# MainBoard_v2_0_RevB.net
KiCad netlist of a schematic drawn in EAGLE
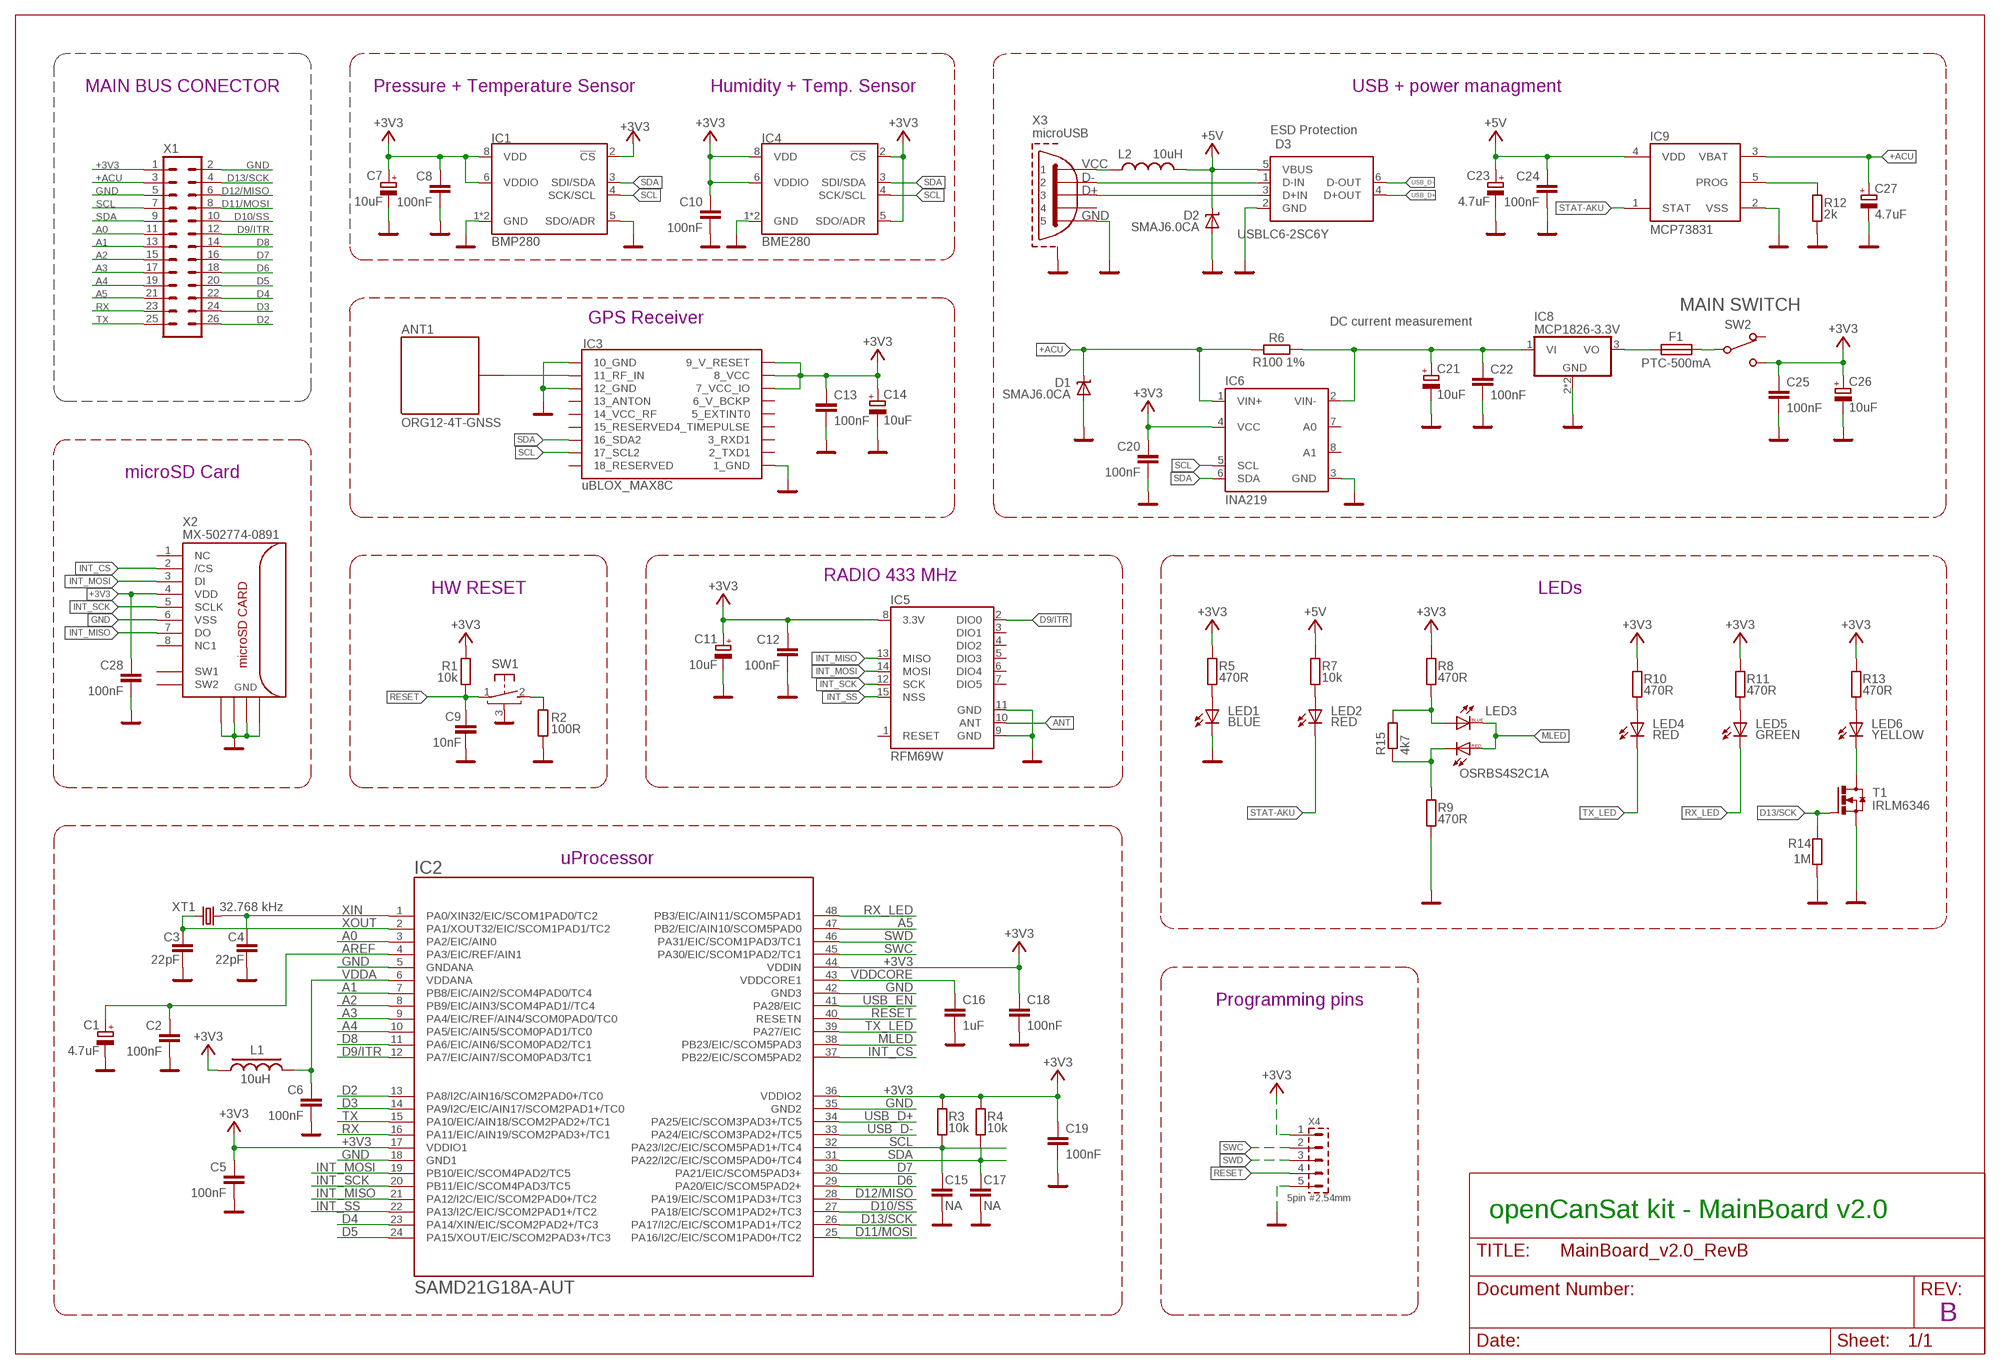
[diagram p0: schematic, sheet 1]

(export (version "E")
  (design (tool "Eeschema 10.0.6"))
  (components
    (comp (ref "ANT1")
      (value "ORG12-4T-GNSS")
      (footprint "eagle-import:ANT_GPS_12X12")
      (libsource (lib "eagle-import") (part "GPS_ANT"))
    )
    (comp (ref "C1")
      (value "4.7uF")
      (footprint "eagle-import:SMC_A")
      (libsource (lib "eagle-import") (part "CPOL-EUSMCA"))
    )
    (comp (ref "C2")
      (value "100nF")
      (footprint "eagle-import:C0603")
      (libsource (lib "eagle-import") (part "C-EUC0603"))
    )
    (comp (ref "C3")
      (value "22pF")
      (footprint "eagle-import:C0603")
      (libsource (lib "eagle-import") (part "C-EUC0603"))
    )
    (comp (ref "C4")
      (value "22pF")
      (footprint "eagle-import:C0603")
      (libsource (lib "eagle-import") (part "C-EUC0603"))
    )
    (comp (ref "C5")
      (value "100nF")
      (footprint "eagle-import:C0603")
      (libsource (lib "eagle-import") (part "C-EUC0603"))
    )
    (comp (ref "C6")
      (value "100nF")
      (footprint "eagle-import:C0603")
      (libsource (lib "eagle-import") (part "C-EUC0603"))
    )
    (comp (ref "C7")
      (value "10uF")
      (footprint "eagle-import:SMC_A")
      (libsource (lib "eagle-import") (part "CPOL-EUSMCA"))
    )
    (comp (ref "C8")
      (value "100nF")
      (footprint "eagle-import:C0603")
      (libsource (lib "eagle-import") (part "C-EUC0603"))
    )
    (comp (ref "C9")
      (value "10nF")
      (footprint "eagle-import:C0603")
      (libsource (lib "eagle-import") (part "C-EUC0603"))
    )
    (comp (ref "C10")
      (value "100nF")
      (footprint "eagle-import:C0603")
      (libsource (lib "eagle-import") (part "C-EUC0603"))
    )
    (comp (ref "C11")
      (value "10uF")
      (footprint "eagle-import:SMC_A")
      (libsource (lib "eagle-import") (part "CPOL-EUSMCA"))
    )
    (comp (ref "C12")
      (value "100nF")
      (footprint "eagle-import:C0603")
      (libsource (lib "eagle-import") (part "C-EUC0603"))
    )
    (comp (ref "C13")
      (value "100nF")
      (footprint "eagle-import:C0603")
      (libsource (lib "eagle-import") (part "C-EUC0603"))
    )
    (comp (ref "C14")
      (value "10uF")
      (footprint "eagle-import:SMC_A")
      (libsource (lib "eagle-import") (part "CPOL-EUSMCA"))
    )
    (comp (ref "C15")
      (value "NA")
      (footprint "eagle-import:C0603")
      (libsource (lib "eagle-import") (part "C-EUC0603"))
    )
    (comp (ref "C16")
      (value "1uF")
      (footprint "eagle-import:C0805")
      (libsource (lib "eagle-import") (part "C-EUC0805"))
    )
    (comp (ref "C17")
      (value "NA")
      (footprint "eagle-import:C0603")
      (libsource (lib "eagle-import") (part "C-EUC0603"))
    )
    (comp (ref "C18")
      (value "100nF")
      (footprint "eagle-import:C0603")
      (libsource (lib "eagle-import") (part "C-EUC0603"))
    )
    (comp (ref "C19")
      (value "100nF")
      (footprint "eagle-import:C0603")
      (libsource (lib "eagle-import") (part "C-EUC0603"))
    )
    (comp (ref "C20")
      (value "100nF")
      (footprint "eagle-import:C0603")
      (libsource (lib "eagle-import") (part "C-EUC0603"))
    )
    (comp (ref "C21")
      (value "10uF")
      (footprint "eagle-import:SMC_B")
      (libsource (lib "eagle-import") (part "CPOL-EUSMCB"))
    )
    (comp (ref "C22")
      (value "100nF")
      (footprint "eagle-import:C0603")
      (libsource (lib "eagle-import") (part "C-EUC0603"))
    )
    (comp (ref "C23")
      (value "4.7uF")
      (footprint "eagle-import:SMC_A")
      (libsource (lib "eagle-import") (part "CPOL-EUSMCA"))
    )
    (comp (ref "C24")
      (value "100nF")
      (footprint "eagle-import:C0603")
      (libsource (lib "eagle-import") (part "C-EUC0603"))
    )
    (comp (ref "C25")
      (value "100nF")
      (footprint "eagle-import:C0603")
      (libsource (lib "eagle-import") (part "C-EUC0603"))
    )
    (comp (ref "C26")
      (value "10uF")
      (footprint "eagle-import:SMC_B")
      (libsource (lib "eagle-import") (part "CPOL-EUSMCB"))
    )
    (comp (ref "C27")
      (value "4.7uF")
      (footprint "eagle-import:SMC_A")
      (libsource (lib "eagle-import") (part "CPOL-EUSMCA"))
    )
    (comp (ref "C28")
      (value "100nF")
      (footprint "eagle-import:C0603")
      (libsource (lib "eagle-import") (part "C-EUC0603"))
    )
    (comp (ref "D1")
      (value "SMAJ6.0CA")
      (footprint "eagle-import:DO214AC")
      (libsource (lib "eagle-import") (part "TRANSILDO214AC"))
    )
    (comp (ref "D2")
      (value "SMAJ6.0CA")
      (footprint "eagle-import:DO214AC")
      (libsource (lib "eagle-import") (part "TRANSILDO214AC"))
    )
    (comp (ref "D3")
      (value "USBLC6-2SC6Y")
      (footprint "eagle-import:SOT95P280X145-6N")
      (fields (field (name "RS_PART_NUMBER") "8805525"))
      (libsource (lib "eagle-import") (part "USBLC6-2SC6Y"))
    )
    (comp (ref "F1")
      (value "PTC-500mA")
      (footprint "eagle-import:1210")
      (libsource (lib "eagle-import") (part "FUZE1210"))
    )
    (comp (ref "IC1")
      (value "BMP280")
      (footprint "eagle-import:LGA-8-2.5X2.5")
      (libsource (lib "eagle-import") (part "BME280"))
    )
    (comp (ref "IC2")
      (value "SAMD21G18A-AUT")
      (footprint "eagle-import:TQFP48-7X7")
      (libsource (lib "eagle-import") (part "1792_SAMD21G18A-AUT"))
    )
    (comp (ref "IC3")
      (value "uBLOX_MAX8C")
      (footprint "eagle-import:UBLOX_MAX-6")
      (libsource (lib "eagle-import") (part "UBLOX_MAX-6"))
    )
    (comp (ref "IC4")
      (value "BME280")
      (footprint "eagle-import:LGA-8-2.5X2.5")
      (libsource (lib "eagle-import") (part "BME280"))
    )
    (comp (ref "IC5")
      (value "RFM69W")
      (footprint "eagle-import:RFM69W-XXXS2")
      (libsource (lib "eagle-import") (part "RFM69HW"))
    )
    (comp (ref "IC6")
      (value "INA219")
      (footprint "eagle-import:SOT23-8")
      (libsource (lib "eagle-import") (part "INA219"))
    )
    (comp (ref "IC8")
      (value "MCP1826-3.3V")
      (footprint "eagle-import:SOT223-3")
      (libsource (lib "eagle-import") (part "MCP1826SOT223-3"))
    )
    (comp (ref "IC9")
      (value "MCP73831")
      (footprint "eagle-import:SOT23-5L")
      (libsource (lib "eagle-import") (part "MCP73831/OT"))
    )
    (comp (ref "L1")
      (value "10uH")
      (footprint "eagle-import:R0805")
      (libsource (lib "eagle-import") (part "L-USL0805"))
    )
    (comp (ref "L2")
      (value "10uH")
      (footprint "eagle-import:R0805")
      (libsource (lib "eagle-import") (part "L-USL0805"))
    )
    (comp (ref "LED1")
      (value "BLUE")
      (footprint "eagle-import:CHIPLED_0603")
      (libsource (lib "eagle-import") (part "LEDCHIPLED_0603"))
    )
    (comp (ref "LED2")
      (value "RED")
      (footprint "eagle-import:CHIPLED_0603")
      (libsource (lib "eagle-import") (part "LEDCHIPLED_0603"))
    )
    (comp (ref "LED3")
      (value "OSRBS4S2C1A")
      (footprint "eagle-import:PLCC4")
      (libsource (lib "eagle-import") (part "OSRBS4S2C1A"))
    )
    (comp (ref "LED4")
      (value "RED")
      (footprint "eagle-import:CHIPLED_0603")
      (libsource (lib "eagle-import") (part "LEDCHIPLED_0603"))
    )
    (comp (ref "LED5")
      (value "GREEN")
      (footprint "eagle-import:CHIPLED_0603")
      (libsource (lib "eagle-import") (part "LEDCHIPLED_0603"))
    )
    (comp (ref "LED6")
      (value "YELLOW")
      (footprint "eagle-import:CHIPLED_0603")
      (libsource (lib "eagle-import") (part "LEDCHIPLED_0603"))
    )
    (comp (ref "R1")
      (value "10k")
      (footprint "eagle-import:R0603")
      (libsource (lib "eagle-import") (part "R-EU_R0603"))
    )
    (comp (ref "R2")
      (value "100R")
      (footprint "eagle-import:R0603")
      (libsource (lib "eagle-import") (part "R-EU_R0603"))
    )
    (comp (ref "R3")
      (value "10k")
      (footprint "eagle-import:R0603")
      (libsource (lib "eagle-import") (part "R-EU_R0603"))
    )
    (comp (ref "R4")
      (value "10k")
      (footprint "eagle-import:R0603")
      (libsource (lib "eagle-import") (part "R-EU_R0603"))
    )
    (comp (ref "R5")
      (value "470R")
      (footprint "eagle-import:R0603")
      (libsource (lib "eagle-import") (part "R-EU_R0603"))
    )
    (comp (ref "R6")
      (value "R100 1%")
      (footprint "eagle-import:R2010")
      (libsource (lib "eagle-import") (part "R-EU_R2010"))
    )
    (comp (ref "R7")
      (value "10k")
      (footprint "eagle-import:R0603")
      (libsource (lib "eagle-import") (part "R-EU_R0603"))
    )
    (comp (ref "R8")
      (value "470R")
      (footprint "eagle-import:R0603")
      (libsource (lib "eagle-import") (part "R-EU_R0603"))
    )
    (comp (ref "R9")
      (value "470R")
      (footprint "eagle-import:R0603")
      (libsource (lib "eagle-import") (part "R-EU_R0603"))
    )
    (comp (ref "R10")
      (value "470R")
      (footprint "eagle-import:R0603")
      (libsource (lib "eagle-import") (part "R-EU_R0603"))
    )
    (comp (ref "R11")
      (value "470R")
      (footprint "eagle-import:R0603")
      (libsource (lib "eagle-import") (part "R-EU_R0603"))
    )
    (comp (ref "R12")
      (value "2k")
      (footprint "eagle-import:R0603")
      (libsource (lib "eagle-import") (part "R-EU_R0603"))
    )
    (comp (ref "R13")
      (value "470R")
      (footprint "eagle-import:R0603")
      (libsource (lib "eagle-import") (part "R-EU_R0603"))
    )
    (comp (ref "R14")
      (value "1M")
      (footprint "eagle-import:R0603")
      (libsource (lib "eagle-import") (part "R-EU_R0603"))
    )
    (comp (ref "R15")
      (value "4k7")
      (footprint "eagle-import:R0603")
      (libsource (lib "eagle-import") (part "R-EU_R0603"))
    )
    (comp (ref "SW1")
      (value "B3U-3100P")
      (footprint "eagle-import:B3U-3100PM")
      (libsource (lib "eagle-import") (part "B3U-3100P"))
    )
    (comp (ref "SW2")
      (value "MSS-1290")
      (footprint "eagle-import:MSS-1290")
      (libsource (lib "eagle-import") (part "MSS-1290"))
    )
    (comp (ref "T1")
      (value "IRLM6346")
      (footprint "eagle-import:SOT23")
      (libsource (lib "eagle-import") (part "IRLML6346"))
    )
    (comp (ref "X1")
      (value "MA13-2SMD")
      (footprint "eagle-import:MA13-2")
      (libsource (lib "eagle-import") (part "MA13-2SMD"))
    )
    (comp (ref "X2")
      (value "MX-502774-0891")
      (footprint "eagle-import:502774-0891")
      (libsource (lib "eagle-import") (part "MICROSD"))
    )
    (comp (ref "X3")
      (value "microUSB")
      (footprint "eagle-import:1981568-MICROUSB")
      (libsource (lib "eagle-import") (part "MICROUSB1981568"))
    )
    (comp (ref "X4")
      (value "5pin #2.54mm")
      (footprint "eagle-import:PIN5")
      (libsource (lib "eagle-import") (part "S1G5_JUMPSMD"))
    )
    (comp (ref "XT1")
      (value "32.768 kHz")
      (footprint "eagle-import:XTAL35X15")
      (libsource (lib "eagle-import") (part "XTAL32KHZ"))
    )
  )
  (nets
    (net (code "1") (name "+3V3") (class "Default")
      (node (ref "C10") (pin "1") (pinfunction "1_1") (pintype "passive"))
      (node (ref "C11") (pin "+") (pinfunction "+_+") (pintype "passive"))
      (node (ref "C12") (pin "1") (pinfunction "1_1") (pintype "passive"))
      (node (ref "C13") (pin "1") (pinfunction "1_1") (pintype "passive"))
      (node (ref "C14") (pin "+") (pinfunction "+_+") (pintype "passive"))
      (node (ref "C18") (pin "1") (pinfunction "1_1") (pintype "passive"))
      (node (ref "C19") (pin "1") (pinfunction "1_1") (pintype "passive"))
      (node (ref "C20") (pin "1") (pinfunction "1_1") (pintype "passive"))
      (node (ref "C25") (pin "1") (pinfunction "1_1") (pintype "passive"))
      (node (ref "C26") (pin "+") (pinfunction "+_+") (pintype "passive"))
      (node (ref "C28") (pin "1") (pinfunction "1_1") (pintype "passive"))
      (node (ref "C5") (pin "1") (pinfunction "1_1") (pintype "passive"))
      (node (ref "C7") (pin "+") (pinfunction "+_+") (pintype "passive"))
      (node (ref "C8") (pin "1") (pinfunction "1_1") (pintype "passive"))
      (node (ref "IC1") (pin "2") (pinfunction "~{CS}_2") (pintype "bidirectional"))
      (node (ref "IC1") (pin "6") (pinfunction "VDDIO_6") (pintype "bidirectional"))
      (node (ref "IC1") (pin "8") (pinfunction "VDD_8") (pintype "bidirectional"))
      (node (ref "IC2") (pin "17") (pinfunction "VDDIO1_17") (pintype "power_in"))
      (node (ref "IC2") (pin "36") (pinfunction "VDDIO2_36") (pintype "power_in"))
      (node (ref "IC2") (pin "44") (pinfunction "VDDIN_44") (pintype "power_in"))
      (node (ref "IC3") (pin "7_VCC_IO") (pinfunction "7_VCC_IO_7_VCC_IO") (pintype "power_in"))
      (node (ref "IC3") (pin "8_VCC") (pinfunction "8_VCC_8_VCC") (pintype "power_in"))
      (node (ref "IC3") (pin "9_V_RESET") (pinfunction "9_V_RESET_9_V_RESET") (pintype "power_in"))
      (node (ref "IC4") (pin "2") (pinfunction "~{CS}_2") (pintype "bidirectional"))
      (node (ref "IC4") (pin "5") (pinfunction "SDO/ADR_5") (pintype "bidirectional"))
      (node (ref "IC4") (pin "6") (pinfunction "VDDIO_6") (pintype "bidirectional"))
      (node (ref "IC4") (pin "8") (pinfunction "VDD_8") (pintype "bidirectional"))
      (node (ref "IC5") (pin "8") (pinfunction "3.3V_8") (pintype "power_in"))
      (node (ref "IC6") (pin "4") (pinfunction "VCC_4") (pintype "bidirectional"))
      (node (ref "L1") (pin "1") (pinfunction "1_1") (pintype "passive"))
      (node (ref "R1") (pin "2") (pinfunction "2_2") (pintype "passive"))
      (node (ref "R10") (pin "2") (pinfunction "2_2") (pintype "passive"))
      (node (ref "R11") (pin "2") (pinfunction "2_2") (pintype "passive"))
      (node (ref "R13") (pin "2") (pinfunction "2_2") (pintype "passive"))
      (node (ref "R3") (pin "2") (pinfunction "2_2") (pintype "passive"))
      (node (ref "R4") (pin "2") (pinfunction "2_2") (pintype "passive"))
      (node (ref "R5") (pin "2") (pinfunction "2_2") (pintype "passive"))
      (node (ref "R8") (pin "2") (pinfunction "2_2") (pintype "passive"))
      (node (ref "SW2") (pin "1") (pinfunction "1-NO_1") (pintype "passive"))
      (node (ref "X1") (pin "1") (pinfunction "1_1") (pintype "passive"))
      (node (ref "X2") (pin "4") (pinfunction "VDD_4") (pintype "bidirectional"))
      (node (ref "X4") (pin "1") (pinfunction "1_1") (pintype "passive"))
    )
    (net (code "2") (name "+5V") (class "Default")
      (node (ref "C23") (pin "+") (pinfunction "+_+") (pintype "passive"))
      (node (ref "C24") (pin "1") (pinfunction "1_1") (pintype "passive"))
      (node (ref "D2") (pin "C") (pinfunction "C_C") (pintype "passive"))
      (node (ref "D3") (pin "5") (pinfunction "VBUS_5") (pintype "input"))
      (node (ref "IC9") (pin "4") (pinfunction "VDD_4") (pintype "power_in"))
      (node (ref "L2") (pin "2") (pinfunction "2_2") (pintype "passive"))
      (node (ref "R7") (pin "2") (pinfunction "2_2") (pintype "passive"))
    )
    (net (code "3") (name "+ACU") (class "Default")
      (node (ref "C27") (pin "+") (pinfunction "+_+") (pintype "passive"))
      (node (ref "D1") (pin "C") (pinfunction "C_C") (pintype "passive"))
      (node (ref "IC6") (pin "1") (pinfunction "VIN+_1") (pintype "bidirectional"))
      (node (ref "IC9") (pin "3") (pinfunction "VBAT_3") (pintype "bidirectional"))
      (node (ref "R6") (pin "1") (pinfunction "1_1") (pintype "passive"))
      (node (ref "X1") (pin "3") (pinfunction "3_3") (pintype "passive"))
    )
    (net (code "4") (name "/A0") (class "Default")
      (node (ref "IC2") (pin "3") (pinfunction "PA2/EIC/AIN0_3") (pintype "bidirectional"))
      (node (ref "X1") (pin "11") (pinfunction "11_11") (pintype "passive"))
    )
    (net (code "5") (name "/A1") (class "Default")
      (node (ref "IC2") (pin "7") (pinfunction "PB8/EIC/AIN2/SCOM4PAD0/TC4_7") (pintype "bidirectional"))
      (node (ref "X1") (pin "13") (pinfunction "13_13") (pintype "passive"))
    )
    (net (code "6") (name "/A2") (class "Default")
      (node (ref "IC2") (pin "8") (pinfunction "PB9/EIC/AIN3/SCOM4PAD1//TC4_8") (pintype "bidirectional"))
      (node (ref "X1") (pin "15") (pinfunction "15_15") (pintype "passive"))
    )
    (net (code "7") (name "/A3") (class "Default")
      (node (ref "IC2") (pin "9") (pinfunction "PA4/EIC/REF/AIN4/SCOM0PAD0/TC0_9") (pintype "bidirectional"))
      (node (ref "X1") (pin "17") (pinfunction "17_17") (pintype "passive"))
    )
    (net (code "8") (name "/A4") (class "Default")
      (node (ref "IC2") (pin "10") (pinfunction "PA5/EIC/AIN5/SCOM0PAD1/TC0_10") (pintype "bidirectional"))
      (node (ref "X1") (pin "19") (pinfunction "19_19") (pintype "passive"))
    )
    (net (code "9") (name "/A5") (class "Default")
      (node (ref "IC2") (pin "47") (pinfunction "PB2/EIC/AIN10/SCOM5PAD0_47") (pintype "bidirectional"))
      (node (ref "X1") (pin "21") (pinfunction "21_21") (pintype "passive"))
    )
    (net (code "10") (name "/AREF") (class "Default")
      (node (ref "C1") (pin "+") (pinfunction "+_+") (pintype "passive"))
      (node (ref "C2") (pin "1") (pinfunction "1_1") (pintype "passive"))
      (node (ref "IC2") (pin "4") (pinfunction "PA3/EIC/REF/AIN1_4") (pintype "bidirectional"))
    )
    (net (code "11") (name "/D2") (class "Default")
      (node (ref "IC2") (pin "13") (pinfunction "PA8/I2C/AIN16/SCOM2PAD0+/TC0_13") (pintype "bidirectional"))
      (node (ref "X1") (pin "26") (pinfunction "26_26") (pintype "passive"))
    )
    (net (code "12") (name "/D3") (class "Default")
      (node (ref "IC2") (pin "14") (pinfunction "PA9/I2C/EIC/AIN17/SCOM2PAD1+/TC0_14") (pintype "bidirectional"))
      (node (ref "X1") (pin "24") (pinfunction "24_24") (pintype "passive"))
    )
    (net (code "13") (name "/D4") (class "Default")
      (node (ref "IC2") (pin "23") (pinfunction "PA14/XIN/EIC/SCOM2PAD2+/TC3_23") (pintype "bidirectional"))
      (node (ref "X1") (pin "22") (pinfunction "22_22") (pintype "passive"))
    )
    (net (code "14") (name "/D5") (class "Default")
      (node (ref "IC2") (pin "24") (pinfunction "PA15/XOUT/EIC/SCOM2PAD3+/TC3_24") (pintype "bidirectional"))
      (node (ref "X1") (pin "20") (pinfunction "20_20") (pintype "passive"))
    )
    (net (code "15") (name "/D6") (class "Default")
      (node (ref "IC2") (pin "29") (pinfunction "PA20/EIC/SCOM5PAD2+_29") (pintype "bidirectional"))
      (node (ref "X1") (pin "18") (pinfunction "18_18") (pintype "passive"))
    )
    (net (code "16") (name "/D7") (class "Default")
      (node (ref "IC2") (pin "30") (pinfunction "PA21/EIC/SCOM5PAD3+_30") (pintype "bidirectional"))
      (node (ref "X1") (pin "16") (pinfunction "16_16") (pintype "passive"))
    )
    (net (code "17") (name "/D8") (class "Default")
      (node (ref "IC2") (pin "11") (pinfunction "PA6/EIC/AIN6/SCOM0PAD2/TC1_11") (pintype "bidirectional"))
      (node (ref "X1") (pin "14") (pinfunction "14_14") (pintype "passive"))
    )
    (net (code "18") (name "/D10{slash}SS") (class "Default")
      (node (ref "IC2") (pin "27") (pinfunction "PA18/EIC/SCOM1PAD2+/TC3_27") (pintype "bidirectional"))
      (node (ref "X1") (pin "10") (pinfunction "10_10") (pintype "passive"))
    )
    (net (code "19") (name "/D11{slash}MOSI") (class "Default")
      (node (ref "IC2") (pin "25") (pinfunction "PA16/I2C/EIC/SCOM1PAD0+/TC2_25") (pintype "bidirectional"))
      (node (ref "X1") (pin "8") (pinfunction "8_8") (pintype "passive"))
    )
    (net (code "20") (name "/D12{slash}MISO") (class "Default")
      (node (ref "IC2") (pin "28") (pinfunction "PA19/EIC/SCOM1PAD3+/TC3_28") (pintype "bidirectional"))
      (node (ref "X1") (pin "6") (pinfunction "6_6") (pintype "passive"))
    )
    (net (code "21") (name "/RX") (class "Default")
      (node (ref "IC2") (pin "16") (pinfunction "PA11/EIC/AIN19/SCOM2PAD3+/TC1_16") (pintype "bidirectional"))
      (node (ref "X1") (pin "23") (pinfunction "23_23") (pintype "passive"))
    )
    (net (code "22") (name "/TX") (class "Default")
      (node (ref "IC2") (pin "15") (pinfunction "PA10/EIC/AIN18/SCOM2PAD2+/TC1_15") (pintype "bidirectional"))
      (node (ref "X1") (pin "25") (pinfunction "25_25") (pintype "passive"))
    )
    (net (code "23") (name "/USB_EN") (class "Default")
      (node (ref "IC2") (pin "41") (pinfunction "PA28/EIC_41") (pintype "bidirectional"))
    )
    (net (code "24") (name "/VDDA") (class "Default")
      (node (ref "C6") (pin "1") (pinfunction "1_1") (pintype "passive"))
      (node (ref "IC2") (pin "6") (pinfunction "VDDANA_6") (pintype "power_in"))
      (node (ref "L1") (pin "2") (pinfunction "2_2") (pintype "passive"))
    )
    (net (code "25") (name "/VDDCORE") (class "Default")
      (node (ref "C16") (pin "1") (pinfunction "1_1") (pintype "passive"))
      (node (ref "IC2") (pin "43") (pinfunction "VDDCORE1_43") (pintype "input"))
    )
    (net (code "26") (name "/XIN") (class "Default")
      (node (ref "C4") (pin "1") (pinfunction "1_1") (pintype "passive"))
      (node (ref "IC2") (pin "1") (pinfunction "PA0/XIN32/EIC/SCOM1PAD0/TC2_1") (pintype "bidirectional"))
      (node (ref "XT1") (pin "2") (pinfunction "2_2") (pintype "passive"))
    )
    (net (code "27") (name "/XOUT") (class "Default")
      (node (ref "C3") (pin "1") (pinfunction "1_1") (pintype "passive"))
      (node (ref "IC2") (pin "2") (pinfunction "PA1/XOUT32/EIC/SCOM1PAD1/TC2_2") (pintype "bidirectional"))
      (node (ref "XT1") (pin "1") (pinfunction "1_1") (pintype "passive"))
    )
    (net (code "28") (name "ANT") (class "Default")
      (node (ref "IC5") (pin "10") (pinfunction "ANT_10") (pintype "passive"))
    )
    (net (code "29") (name "D9{slash}ITR") (class "Default")
      (node (ref "IC2") (pin "12") (pinfunction "PA7/EIC/AIN7/SCOM0PAD3/TC1_12") (pintype "bidirectional"))
      (node (ref "IC5") (pin "2") (pinfunction "DIO0_2") (pintype "bidirectional"))
      (node (ref "X1") (pin "12") (pinfunction "12_12") (pintype "passive"))
    )
    (net (code "30") (name "D13{slash}SCK") (class "Default")
      (node (ref "IC2") (pin "26") (pinfunction "PA17/I2C/EIC/SCOM1PAD1+/TC2_26") (pintype "bidirectional"))
      (node (ref "R14") (pin "2") (pinfunction "2_2") (pintype "passive"))
      (node (ref "T1") (pin "1") (pinfunction "G_1") (pintype "passive"))
      (node (ref "X1") (pin "4") (pinfunction "4_4") (pintype "passive"))
    )
    (net (code "31") (name "GND") (class "Default")
      (node (ref "C1") (pin "-") (pinfunction "-_-") (pintype "passive"))
      (node (ref "C10") (pin "2") (pinfunction "2_2") (pintype "passive"))
      (node (ref "C11") (pin "-") (pinfunction "-_-") (pintype "passive"))
      (node (ref "C12") (pin "2") (pinfunction "2_2") (pintype "passive"))
      (node (ref "C13") (pin "2") (pinfunction "2_2") (pintype "passive"))
      (node (ref "C14") (pin "-") (pinfunction "-_-") (pintype "passive"))
      (node (ref "C15") (pin "2") (pinfunction "2_2") (pintype "passive"))
      (node (ref "C16") (pin "2") (pinfunction "2_2") (pintype "passive"))
      (node (ref "C17") (pin "2") (pinfunction "2_2") (pintype "passive"))
      (node (ref "C18") (pin "2") (pinfunction "2_2") (pintype "passive"))
      (node (ref "C19") (pin "2") (pinfunction "2_2") (pintype "passive"))
      (node (ref "C2") (pin "2") (pinfunction "2_2") (pintype "passive"))
      (node (ref "C20") (pin "2") (pinfunction "2_2") (pintype "passive"))
      (node (ref "C21") (pin "-") (pinfunction "-_-") (pintype "passive"))
      (node (ref "C22") (pin "2") (pinfunction "2_2") (pintype "passive"))
      (node (ref "C23") (pin "-") (pinfunction "-_-") (pintype "passive"))
      (node (ref "C24") (pin "2") (pinfunction "2_2") (pintype "passive"))
      (node (ref "C25") (pin "2") (pinfunction "2_2") (pintype "passive"))
      (node (ref "C26") (pin "-") (pinfunction "-_-") (pintype "passive"))
      (node (ref "C27") (pin "-") (pinfunction "-_-") (pintype "passive"))
      (node (ref "C28") (pin "2") (pinfunction "2_2") (pintype "passive"))
      (node (ref "C3") (pin "2") (pinfunction "2_2") (pintype "passive"))
      (node (ref "C4") (pin "2") (pinfunction "2_2") (pintype "passive"))
      (node (ref "C5") (pin "2") (pinfunction "2_2") (pintype "passive"))
      (node (ref "C6") (pin "2") (pinfunction "2_2") (pintype "passive"))
      (node (ref "C7") (pin "-") (pinfunction "-_-") (pintype "passive"))
      (node (ref "C8") (pin "2") (pinfunction "2_2") (pintype "passive"))
      (node (ref "C9") (pin "2") (pinfunction "2_2") (pintype "passive"))
      (node (ref "D1") (pin "A") (pinfunction "A_A") (pintype "passive"))
      (node (ref "D2") (pin "A") (pinfunction "A_A") (pintype "passive"))
      (node (ref "D3") (pin "2") (pinfunction "GND_2") (pintype "input"))
      (node (ref "IC1") (pin "1") (pinfunction "GND_1") (pintype "bidirectional"))
      (node (ref "IC1") (pin "5") (pinfunction "SDO/ADR_5") (pintype "bidirectional"))
      (node (ref "IC1") (pin "7") (pinfunction "GND_7") (pintype "bidirectional"))
      (node (ref "IC2") (pin "18") (pinfunction "GND1_18") (pintype "power_in"))
      (node (ref "IC2") (pin "35") (pinfunction "GND2_35") (pintype "power_in"))
      (node (ref "IC2") (pin "42") (pinfunction "GND3_42") (pintype "power_in"))
      (node (ref "IC2") (pin "5") (pinfunction "GNDANA_5") (pintype "power_in"))
      (node (ref "IC3") (pin "10_GND") (pinfunction "10_GND_10_GND") (pintype "power_in"))
      (node (ref "IC3") (pin "12_GND") (pinfunction "12_GND_12_GND") (pintype "power_in"))
      (node (ref "IC3") (pin "1_GND") (pinfunction "1_GND_1_GND") (pintype "power_in"))
      (node (ref "IC4") (pin "1") (pinfunction "GND_1") (pintype "bidirectional"))
      (node (ref "IC4") (pin "7") (pinfunction "GND_7") (pintype "bidirectional"))
      (node (ref "IC5") (pin "11") (pinfunction "GND_11") (pintype "power_in"))
      (node (ref "IC5") (pin "9") (pinfunction "GND_9") (pintype "power_in"))
      (node (ref "IC6") (pin "3") (pinfunction "GND_3") (pintype "bidirectional"))
      (node (ref "IC8") (pin "2") (pinfunction "GND_2") (pintype "passive"))
      (node (ref "IC8") (pin "4") (pinfunction "GND_4") (pintype "passive"))
      (node (ref "IC9") (pin "2") (pinfunction "VSS_2") (pintype "power_in"))
      (node (ref "LED1") (pin "C") (pinfunction "C_C") (pintype "passive"))
      (node (ref "R12") (pin "1") (pinfunction "1_1") (pintype "passive"))
      (node (ref "R14") (pin "1") (pinfunction "1_1") (pintype "passive"))
      (node (ref "R2") (pin "1") (pinfunction "1_1") (pintype "passive"))
      (node (ref "R9") (pin "1") (pinfunction "1_1") (pintype "passive"))
      (node (ref "SW1") (pin "3") (pinfunction "3_3") (pintype "passive"))
      (node (ref "T1") (pin "2") (pinfunction "S_2") (pintype "passive"))
      (node (ref "X1") (pin "2") (pinfunction "2_2") (pintype "passive"))
      (node (ref "X1") (pin "5") (pinfunction "5_5") (pintype "passive"))
      (node (ref "X2") (pin "6") (pinfunction "VSS_6") (pintype "bidirectional"))
      (node (ref "X2") (pin "GND1") (pinfunction "GND1_GND1") (pintype "bidirectional"))
      (node (ref "X2") (pin "GND2") (pinfunction "GND2_GND2") (pintype "bidirectional"))
      (node (ref "X2") (pin "GND3") (pinfunction "GND3_GND3") (pintype "bidirectional"))
      (node (ref "X2") (pin "GND4") (pinfunction "GND4_GND4") (pintype "bidirectional"))
      (node (ref "X3") (pin "P$10") (pinfunction "SHIELD_P$10") (pintype "bidirectional"))
      (node (ref "X3") (pin "P$11") (pinfunction "SHIELD_P$11") (pintype "bidirectional"))
      (node (ref "X3") (pin "P$5") (pinfunction "5_P$5") (pintype "passive"))
      (node (ref "X3") (pin "P$6") (pinfunction "SHIELD_P$6") (pintype "bidirectional"))
      (node (ref "X3") (pin "P$7") (pinfunction "SHIELD_P$7") (pintype "bidirectional"))
      (node (ref "X3") (pin "P$8") (pinfunction "SHIELD_P$8") (pintype "bidirectional"))
      (node (ref "X3") (pin "P$9") (pinfunction "SHIELD_P$9") (pintype "bidirectional"))
      (node (ref "X4") (pin "5") (pinfunction "5_5") (pintype "passive"))
    )
    (net (code "32") (name "INT_CS") (class "Default")
      (node (ref "IC2") (pin "37") (pinfunction "PB22/EIC/SCOM5PAD2_37") (pintype "bidirectional"))
      (node (ref "X2") (pin "2") (pinfunction "/CS_2") (pintype "bidirectional"))
    )
    (net (code "33") (name "INT_MISO") (class "Default")
      (node (ref "IC2") (pin "21") (pinfunction "PA12/I2C/EIC/SCOM2PAD0+/TC2_21") (pintype "bidirectional"))
      (node (ref "IC5") (pin "13") (pinfunction "MISO_13") (pintype "bidirectional"))
      (node (ref "X2") (pin "7") (pinfunction "DO_7") (pintype "bidirectional"))
    )
    (net (code "34") (name "INT_MOSI") (class "Default")
      (node (ref "IC2") (pin "19") (pinfunction "PB10/EIC/SCOM4PAD2/TC5_19") (pintype "bidirectional"))
      (node (ref "IC5") (pin "14") (pinfunction "MOSI_14") (pintype "input"))
      (node (ref "X2") (pin "3") (pinfunction "DI_3") (pintype "bidirectional"))
    )
    (net (code "35") (name "INT_SCK") (class "Default")
      (node (ref "IC2") (pin "20") (pinfunction "PB11/EIC/SCOM4PAD3/TC5_20") (pintype "bidirectional"))
      (node (ref "IC5") (pin "12") (pinfunction "SCK_12") (pintype "input"))
      (node (ref "X2") (pin "5") (pinfunction "SCLK_5") (pintype "bidirectional"))
    )
    (net (code "36") (name "INT_SS") (class "Default")
      (node (ref "IC2") (pin "22") (pinfunction "PA13/I2C/EIC/SCOM2PAD1+/TC2_22") (pintype "bidirectional"))
      (node (ref "IC5") (pin "15") (pinfunction "NSS_15") (pintype "input"))
    )
    (net (code "37") (name "MLED") (class "Default")
      (node (ref "IC2") (pin "38") (pinfunction "PB23/EIC/SCOM5PAD3_38") (pintype "bidirectional"))
      (node (ref "LED3") (pin "3") (pinfunction "C-B_3") (pintype "passive"))
      (node (ref "LED3") (pin "4") (pinfunction "A-R_4") (pintype "passive"))
    )
    (net (code "38") (name "Net-(ANT1-PadANT_GPS)") (class "Default")
      (node (ref "ANT1") (pin "ANT_GPS") (pinfunction "ANT_GPS_ANT_GPS") (pintype "bidirectional"))
      (node (ref "IC3") (pin "11_RF_IN") (pinfunction "11_RF_IN_11_RF_IN") (pintype "bidirectional"))
    )
    (net (code "39") (name "Net-(D3-D+IN)") (class "Default")
      (node (ref "D3") (pin "3") (pinfunction "D+IN_3") (pintype "input"))
      (node (ref "X3") (pin "P$3") (pinfunction "3_P$3") (pintype "passive"))
    )
    (net (code "40") (name "Net-(D3-D-IN)") (class "Default")
      (node (ref "D3") (pin "1") (pinfunction "D-IN_1") (pintype "input"))
      (node (ref "X3") (pin "P$2") (pinfunction "2_P$2") (pintype "passive"))
    )
    (net (code "41") (name "Net-(F1-1)") (class "Default")
      (node (ref "F1") (pin "P$1") (pinfunction "1_P$1") (pintype "bidirectional"))
      (node (ref "IC8") (pin "3") (pinfunction "VO_3") (pintype "passive"))
    )
    (net (code "42") (name "Net-(F1-2)") (class "Default")
      (node (ref "F1") (pin "P$2") (pinfunction "2_P$2") (pintype "bidirectional"))
      (node (ref "SW2") (pin "2") (pinfunction "2-COM_2") (pintype "passive"))
    )
    (net (code "43") (name "Net-(IC6-VIN-)") (class "Default")
      (node (ref "C21") (pin "+") (pinfunction "+_+") (pintype "passive"))
      (node (ref "C22") (pin "1") (pinfunction "1_1") (pintype "passive"))
      (node (ref "IC6") (pin "2") (pinfunction "VIN-_2") (pintype "bidirectional"))
      (node (ref "IC8") (pin "1") (pinfunction "VI_1") (pintype "input"))
      (node (ref "R6") (pin "2") (pinfunction "2_2") (pintype "passive"))
    )
    (net (code "44") (name "Net-(IC9-PROG)") (class "Default")
      (node (ref "IC9") (pin "5") (pinfunction "PROG_5") (pintype "input"))
      (node (ref "R12") (pin "2") (pinfunction "2_2") (pintype "passive"))
    )
    (net (code "45") (name "Net-(LED1-PadA)") (class "Default")
      (node (ref "LED1") (pin "A") (pinfunction "A_A") (pintype "passive"))
      (node (ref "R5") (pin "1") (pinfunction "1_1") (pintype "passive"))
    )
    (net (code "46") (name "Net-(LED2-PadA)") (class "Default")
      (node (ref "LED2") (pin "A") (pinfunction "A_A") (pintype "passive"))
      (node (ref "R7") (pin "1") (pinfunction "1_1") (pintype "passive"))
    )
    (net (code "47") (name "Net-(LED3-A-B)") (class "Default")
      (node (ref "LED3") (pin "2") (pinfunction "A-B_2") (pintype "passive"))
      (node (ref "R15") (pin "2") (pinfunction "2_2") (pintype "passive"))
      (node (ref "R8") (pin "1") (pinfunction "1_1") (pintype "passive"))
    )
    (net (code "48") (name "Net-(LED3-C-R)") (class "Default")
      (node (ref "LED3") (pin "1") (pinfunction "C-R_1") (pintype "passive"))
      (node (ref "R15") (pin "1") (pinfunction "1_1") (pintype "passive"))
      (node (ref "R9") (pin "2") (pinfunction "2_2") (pintype "passive"))
    )
    (net (code "49") (name "Net-(LED4-PadA)") (class "Default")
      (node (ref "LED4") (pin "A") (pinfunction "A_A") (pintype "passive"))
      (node (ref "R10") (pin "1") (pinfunction "1_1") (pintype "passive"))
    )
    (net (code "50") (name "Net-(LED5-PadA)") (class "Default")
      (node (ref "LED5") (pin "A") (pinfunction "A_A") (pintype "passive"))
      (node (ref "R11") (pin "1") (pinfunction "1_1") (pintype "passive"))
    )
    (net (code "51") (name "Net-(LED6-PadA)") (class "Default")
      (node (ref "LED6") (pin "A") (pinfunction "A_A") (pintype "passive"))
      (node (ref "R13") (pin "1") (pinfunction "1_1") (pintype "passive"))
    )
    (net (code "52") (name "Net-(SW1-S)") (class "Default")
      (node (ref "R2") (pin "2") (pinfunction "2_2") (pintype "passive"))
      (node (ref "SW1") (pin "2") (pinfunction "S_2") (pintype "passive"))
    )
    (net (code "53") (name "Net-(T1-D)") (class "Default")
      (node (ref "LED6") (pin "C") (pinfunction "C_C") (pintype "passive"))
      (node (ref "T1") (pin "3") (pinfunction "D_3") (pintype "passive"))
    )
    (net (code "54") (name "Net-(X3-1)") (class "Default")
      (node (ref "L2") (pin "1") (pinfunction "1_1") (pintype "passive"))
      (node (ref "X3") (pin "P$1") (pinfunction "1_P$1") (pintype "passive"))
    )
    (net (code "55") (name "RESET") (class "Default")
      (node (ref "C9") (pin "1") (pinfunction "1_1") (pintype "passive"))
      (node (ref "IC2") (pin "40") (pinfunction "RESETN_40") (pintype "bidirectional"))
      (node (ref "R1") (pin "1") (pinfunction "1_1") (pintype "passive"))
      (node (ref "SW1") (pin "1") (pinfunction "P_1") (pintype "passive"))
      (node (ref "X4") (pin "4") (pinfunction "4_4") (pintype "passive"))
    )
    (net (code "56") (name "RX_LED") (class "Default")
      (node (ref "IC2") (pin "48") (pinfunction "PB3/EIC/AIN11/SCOM5PAD1_48") (pintype "bidirectional"))
      (node (ref "LED5") (pin "C") (pinfunction "C_C") (pintype "passive"))
    )
    (net (code "57") (name "SCL") (class "Default")
      (node (ref "C15") (pin "1") (pinfunction "1_1") (pintype "passive"))
      (node (ref "IC1") (pin "4") (pinfunction "SCK/SCL_4") (pintype "bidirectional"))
      (node (ref "IC2") (pin "32") (pinfunction "PA23/I2C/EIC/SCOM5PAD1+/TC4_32") (pintype "bidirectional"))
      (node (ref "IC3") (pin "17_SCL2") (pinfunction "17_SCL2_17_SCL2") (pintype "bidirectional"))
      (node (ref "IC4") (pin "4") (pinfunction "SCK/SCL_4") (pintype "bidirectional"))
      (node (ref "IC6") (pin "5") (pinfunction "SCL_5") (pintype "bidirectional"))
      (node (ref "R3") (pin "1") (pinfunction "1_1") (pintype "passive"))
      (node (ref "X1") (pin "7") (pinfunction "7_7") (pintype "passive"))
    )
    (net (code "58") (name "SDA") (class "Default")
      (node (ref "C17") (pin "1") (pinfunction "1_1") (pintype "passive"))
      (node (ref "IC1") (pin "3") (pinfunction "SDI/SDA_3") (pintype "bidirectional"))
      (node (ref "IC2") (pin "31") (pinfunction "PA22/I2C/EIC/SCOM5PAD0+/TC4_31") (pintype "bidirectional"))
      (node (ref "IC3") (pin "16_SDA2") (pinfunction "16_SDA2_16_SDA2") (pintype "bidirectional"))
      (node (ref "IC4") (pin "3") (pinfunction "SDI/SDA_3") (pintype "bidirectional"))
      (node (ref "IC6") (pin "6") (pinfunction "SDA_6") (pintype "bidirectional"))
      (node (ref "R4") (pin "1") (pinfunction "1_1") (pintype "passive"))
      (node (ref "X1") (pin "9") (pinfunction "9_9") (pintype "passive"))
    )
    (net (code "59") (name "STAT-AKU") (class "Default")
      (node (ref "IC9") (pin "1") (pinfunction "STAT_1") (pintype "output"))
      (node (ref "LED2") (pin "C") (pinfunction "C_C") (pintype "passive"))
    )
    (net (code "60") (name "SWC") (class "Default")
      (node (ref "IC2") (pin "45") (pinfunction "PA30/EIC/SCOM1PAD2/TC1_45") (pintype "bidirectional"))
      (node (ref "X4") (pin "2") (pinfunction "2_2") (pintype "passive"))
    )
    (net (code "61") (name "SWD") (class "Default")
      (node (ref "IC2") (pin "46") (pinfunction "PA31/EIC/SCOM1PAD3/TC1_46") (pintype "bidirectional"))
      (node (ref "X4") (pin "3") (pinfunction "3_3") (pintype "passive"))
    )
    (net (code "62") (name "TX_LED") (class "Default")
      (node (ref "IC2") (pin "39") (pinfunction "PA27/EIC_39") (pintype "bidirectional"))
      (node (ref "LED4") (pin "C") (pinfunction "C_C") (pintype "passive"))
    )
    (net (code "63") (name "USB_D+") (class "Default")
      (node (ref "D3") (pin "4") (pinfunction "D+OUT_4") (pintype "input"))
      (node (ref "IC2") (pin "34") (pinfunction "PA25/EIC/SCOM3PAD3+/TC5_34") (pintype "bidirectional"))
    )
    (net (code "64") (name "USB_D-") (class "Default")
      (node (ref "D3") (pin "6") (pinfunction "D-OUT_6") (pintype "input"))
      (node (ref "IC2") (pin "33") (pinfunction "PA24/EIC/SCOM3PAD2+/TC5_33") (pintype "bidirectional"))
    )
    (net (code "65") (name "unconnected-(IC3-Pad2_TXD1)") (class "Default")
      (node (ref "IC3") (pin "2_TXD1") (pinfunction "2_TXD1_2_TXD1") (pintype "bidirectional"))
    )
    (net (code "66") (name "unconnected-(IC3-Pad3_RXD1)") (class "Default")
      (node (ref "IC3") (pin "3_RXD1") (pinfunction "3_RXD1_3_RXD1") (pintype "bidirectional"))
    )
    (net (code "67") (name "unconnected-(IC3-Pad4_TIMEPULSE)") (class "Default")
      (node (ref "IC3") (pin "4_TIMEPULSE") (pinfunction "4_TIMEPULSE_4_TIMEPULSE") (pintype "bidirectional"))
    )
    (net (code "68") (name "unconnected-(IC3-Pad5_EXTINT0)") (class "Default")
      (node (ref "IC3") (pin "5_EXTINT0") (pinfunction "5_EXTINT0_5_EXTINT0") (pintype "bidirectional"))
    )
    (net (code "69") (name "unconnected-(IC3-Pad6_V_BCKP)") (class "Default")
      (node (ref "IC3") (pin "6_V_BCKP") (pinfunction "6_V_BCKP_6_V_BCKP") (pintype "bidirectional"))
    )
    (net (code "70") (name "unconnected-(IC3-Pad13_ANTON)") (class "Default")
      (node (ref "IC3") (pin "13_ANTON") (pinfunction "13_ANTON_13_ANTON") (pintype "bidirectional"))
    )
    (net (code "71") (name "unconnected-(IC3-Pad14_VCC_RF)") (class "Default")
      (node (ref "IC3") (pin "14_VCC_RF") (pinfunction "14_VCC_RF_14_VCC_RF") (pintype "bidirectional"))
    )
    (net (code "72") (name "unconnected-(IC3-Pad15_RESERVED)") (class "Default")
      (node (ref "IC3") (pin "15_RESERVED") (pinfunction "15_RESERVED_15_RESERVED") (pintype "bidirectional"))
    )
    (net (code "73") (name "unconnected-(IC3-Pad18_RESERVED)") (class "Default")
      (node (ref "IC3") (pin "18_RESERVED") (pinfunction "18_RESERVED_18_RESERVED") (pintype "bidirectional"))
    )
    (net (code "74") (name "unconnected-(IC5-DIO1-Pad3)") (class "Default")
      (node (ref "IC5") (pin "3") (pinfunction "DIO1_3") (pintype "bidirectional"))
    )
    (net (code "75") (name "unconnected-(IC5-DIO2-Pad4)") (class "Default")
      (node (ref "IC5") (pin "4") (pinfunction "DIO2_4") (pintype "bidirectional"))
    )
    (net (code "76") (name "unconnected-(IC5-DIO3-Pad5)") (class "Default")
      (node (ref "IC5") (pin "5") (pinfunction "DIO3_5") (pintype "bidirectional"))
    )
    (net (code "77") (name "unconnected-(IC5-DIO4-Pad6)") (class "Default")
      (node (ref "IC5") (pin "6") (pinfunction "DIO4_6") (pintype "bidirectional"))
    )
    (net (code "78") (name "unconnected-(IC5-DIO5-Pad7)") (class "Default")
      (node (ref "IC5") (pin "7") (pinfunction "DIO5_7") (pintype "bidirectional"))
    )
    (net (code "79") (name "unconnected-(IC5-RESET-Pad1)") (class "Default")
      (node (ref "IC5") (pin "1") (pinfunction "RESET_1") (pintype "input"))
    )
    (net (code "80") (name "unconnected-(IC6-A0-Pad7)") (class "Default")
      (node (ref "IC6") (pin "7") (pinfunction "A0_7") (pintype "bidirectional"))
    )
    (net (code "81") (name "unconnected-(IC6-A1-Pad8)") (class "Default")
      (node (ref "IC6") (pin "8") (pinfunction "A1_8") (pintype "bidirectional"))
    )
    (net (code "82") (name "unconnected-(SW2-3-NC-Pad3)") (class "Default")
      (node (ref "SW2") (pin "3") (pinfunction "3-NC_3") (pintype "passive"))
    )
    (net (code "83") (name "unconnected-(X2-NC-Pad1)") (class "Default")
      (node (ref "X2") (pin "1") (pinfunction "NC_1") (pintype "bidirectional"))
    )
    (net (code "84") (name "unconnected-(X2-NC1-Pad8)") (class "Default")
      (node (ref "X2") (pin "8") (pinfunction "NC1_8") (pintype "bidirectional"))
    )
    (net (code "85") (name "unconnected-(X2-PadSW1)") (class "Default")
      (node (ref "X2") (pin "SW1") (pinfunction "SW1_SW1") (pintype "bidirectional"))
    )
    (net (code "86") (name "unconnected-(X2-PadSW2)") (class "Default")
      (node (ref "X2") (pin "SW2") (pinfunction "SW2_SW2") (pintype "bidirectional"))
    )
    (net (code "87") (name "unconnected-(X3-4-PadP$4)") (class "Default")
      (node (ref "X3") (pin "P$4") (pinfunction "4_P$4") (pintype "passive"))
    )
  )
)
